# DacAmpl.net
KiCad netlist of a schematic drawn in Altium Designer
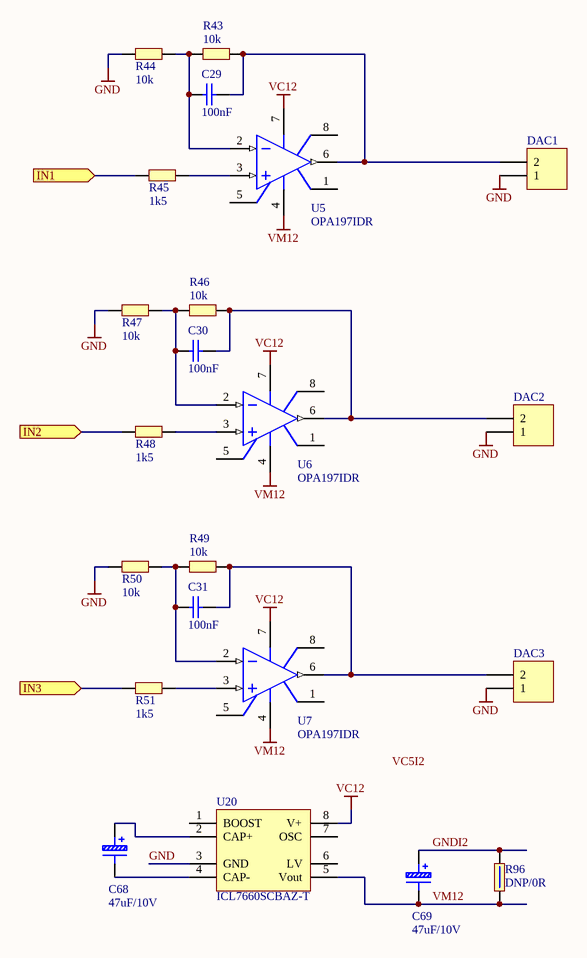
[diagram p0: DacAmpl.SchDoc]

(export (version "E")
  (design (tool "Eeschema 10.0.6"))
  (components
    (comp (ref "C29")
      (value "100nF")
      (footprint "0603C")
      (description "Capacitor,100nF,16V,X7R,10%,0402,YAGEO")
      (libsource (lib "MCD_TOOLS") (part "Cap_100nF_X7R_10%_0402"))
    )
    (comp (ref "C30")
      (value "100nF")
      (footprint "0603C")
      (description "Capacitor,100nF,16V,X7R,10%,0402,YAGEO")
      (libsource (lib "MCD_TOOLS") (part "Cap_100nF_X7R_10%_0402"))
    )
    (comp (ref "C31")
      (value "100nF")
      (footprint "0603C")
      (description "Capacitor,100nF,16V,X7R,10%,0402,YAGEO")
      (libsource (lib "MCD_TOOLS") (part "Cap_100nF_X7R_10%_0402"))
    )
    (comp (ref "C68") (value "47uF/10V") (footprint "CAP_C") (libsource (lib "GkSchlib") (part "CapTantal")))
    (comp (ref "C69") (value "47uF/10V") (footprint "CAP_C") (libsource (lib "GkSchlib") (part "CapTantal")))
    (comp (ref "DAC1")
      (value "Header 2")
      (footprint "JST-B2B-XH-A")
      (description "Header, 2-Pin")
      (fields (field (name "PUBLISHER") "Altium Limited"))
      (libsource (lib "Miscellaneous Connectors") (part "Header 2"))
    )
    (comp (ref "DAC2")
      (value "Header 2")
      (footprint "JST-B2B-XH-A")
      (description "Header, 2-Pin")
      (fields (field (name "PUBLISHER") "Altium Limited"))
      (libsource (lib "Miscellaneous Connectors") (part "Header 2"))
    )
    (comp (ref "DAC3")
      (value "Header 2")
      (footprint "JST-B2B-XH-A")
      (description "Header, 2-Pin")
      (fields (field (name "PUBLISHER") "Altium Limited"))
      (libsource (lib "Miscellaneous Connectors") (part "Header 2"))
    )
    (comp (ref "R43") (value "10k") (footprint "0603R") (libsource (lib "*") (part "RES3")))
    (comp (ref "R44") (value "10k") (footprint "0603R") (libsource (lib "*") (part "RES3")))
    (comp (ref "R45") (value "1k5") (footprint "0603R") (libsource (lib "*") (part "RES3")))
    (comp (ref "R46") (value "10k") (footprint "0603R") (libsource (lib "*") (part "RES3")))
    (comp (ref "R47") (value "10k") (footprint "0603R") (libsource (lib "*") (part "RES3")))
    (comp (ref "R48") (value "1k5") (footprint "0603R") (libsource (lib "*") (part "RES3")))
    (comp (ref "R49") (value "10k") (footprint "0603R") (libsource (lib "*") (part "RES3")))
    (comp (ref "R50") (value "10k") (footprint "0603R") (libsource (lib "*") (part "RES3")))
    (comp (ref "R51") (value "1k5") (footprint "0603R") (libsource (lib "*") (part "RES3")))
    (comp (ref "R96") (value "DNP/0R") (footprint "0603R") (libsource (lib "GkSchlib") (part "RES3Z")))
    (comp (ref "U5")
      (value "OPA197IDR")
      (footprint "SO8")
      (description "FET Operational Amplifier")
      (fields (field (name "PUBLISHER") "Altium Limited"))
      (libsource (lib "Miscellaneous Devices") (part "Op Amp"))
    )
    (comp (ref "U6")
      (value "OPA197IDR")
      (footprint "SO8")
      (description "FET Operational Amplifier")
      (fields (field (name "PUBLISHER") "Altium Limited"))
      (libsource (lib "Miscellaneous Devices") (part "Op Amp"))
    )
    (comp (ref "U7")
      (value "OPA197IDR")
      (footprint "SO8")
      (description "FET Operational Amplifier")
      (fields (field (name "PUBLISHER") "Altium Limited"))
      (libsource (lib "Miscellaneous Devices") (part "Op Amp"))
    )
    (comp (ref "U20")
      (value "ICL7660SCBAZ-T")
      (footprint "SO8")
      (libsource (lib "GkSchlib") (part "ICL7660"))
    )
  )
  (nets
    (net (code "1") (name "/GNDI2") (class "Default")
      (node (ref "C69") (pin "2") (pintype "passive"))
      (node (ref "R96") (pin "1") (pintype "passive"))
    )
    (net (code "2") (name "/IN1") (class "Default") (node (ref "R45") (pin "1") (pintype "passive")))
    (net (code "3") (name "/IN2") (class "Default") (node (ref "R48") (pin "1") (pintype "passive")))
    (net (code "4") (name "/IN3") (class "Default") (node (ref "R51") (pin "1") (pintype "passive")))
    (net (code "6") (name "GND") (class "Default")
      (node (ref "DAC1") (pin "1") (pinfunction "1_1") (pintype "passive"))
      (node (ref "DAC2") (pin "1") (pinfunction "1_1") (pintype "passive"))
      (node (ref "DAC3") (pin "1") (pinfunction "1_1") (pintype "passive"))
      (node (ref "R44") (pin "1") (pintype "passive"))
      (node (ref "R47") (pin "1") (pintype "passive"))
      (node (ref "R50") (pin "1") (pintype "passive"))
      (node (ref "U20") (pin "3") (pinfunction "GND_3") (pintype "passive"))
    )
    (net (code "7") (name "Net-(U5-IN+)") (class "Default")
      (node (ref "R45") (pin "2") (pintype "passive"))
      (node (ref "U5") (pin "3") (pinfunction "IN+_3") (pintype "input"))
    )
    (net (code "8") (name "Net-(U5-IN-)") (class "Default")
      (node (ref "C29") (pin "2") (pinfunction "2_2") (pintype "passive"))
      (node (ref "R43") (pin "1") (pintype "passive"))
      (node (ref "R44") (pin "2") (pintype "passive"))
      (node (ref "U5") (pin "2") (pinfunction "IN-_2") (pintype "input"))
    )
    (net (code "9") (name "Net-(U5-OUT)") (class "Default")
      (node (ref "C29") (pin "1") (pinfunction "1_1") (pintype "passive"))
      (node (ref "DAC1") (pin "2") (pinfunction "2_2") (pintype "passive"))
      (node (ref "R43") (pin "2") (pintype "passive"))
      (node (ref "U5") (pin "6") (pinfunction "OUT_6") (pintype "output"))
    )
    (net (code "10") (name "Net-(U6-IN+)") (class "Default")
      (node (ref "R48") (pin "2") (pintype "passive"))
      (node (ref "U6") (pin "3") (pinfunction "IN+_3") (pintype "input"))
    )
    (net (code "11") (name "Net-(U6-IN-)") (class "Default")
      (node (ref "C30") (pin "2") (pinfunction "2_2") (pintype "passive"))
      (node (ref "R46") (pin "1") (pintype "passive"))
      (node (ref "R47") (pin "2") (pintype "passive"))
      (node (ref "U6") (pin "2") (pinfunction "IN-_2") (pintype "input"))
    )
    (net (code "12") (name "Net-(U6-OUT)") (class "Default")
      (node (ref "C30") (pin "1") (pinfunction "1_1") (pintype "passive"))
      (node (ref "DAC2") (pin "2") (pinfunction "2_2") (pintype "passive"))
      (node (ref "R46") (pin "2") (pintype "passive"))
      (node (ref "U6") (pin "6") (pinfunction "OUT_6") (pintype "output"))
    )
    (net (code "13") (name "Net-(U7-IN+)") (class "Default")
      (node (ref "R51") (pin "2") (pintype "passive"))
      (node (ref "U7") (pin "3") (pinfunction "IN+_3") (pintype "input"))
    )
    (net (code "14") (name "Net-(U7-IN-)") (class "Default")
      (node (ref "C31") (pin "2") (pinfunction "2_2") (pintype "passive"))
      (node (ref "R49") (pin "1") (pintype "passive"))
      (node (ref "R50") (pin "2") (pintype "passive"))
      (node (ref "U7") (pin "2") (pinfunction "IN-_2") (pintype "input"))
    )
    (net (code "15") (name "Net-(U7-OUT)") (class "Default")
      (node (ref "C31") (pin "1") (pinfunction "1_1") (pintype "passive"))
      (node (ref "DAC3") (pin "2") (pinfunction "2_2") (pintype "passive"))
      (node (ref "R49") (pin "2") (pintype "passive"))
      (node (ref "U7") (pin "6") (pinfunction "OUT_6") (pintype "output"))
    )
    (net (code "16") (name "Net-(U20-CAP+)") (class "Default")
      (node (ref "C68") (pin "2") (pintype "passive"))
      (node (ref "U20") (pin "2") (pinfunction "CAP+_2") (pintype "passive"))
    )
    (net (code "17") (name "Net-(U20-CAP-)") (class "Default")
      (node (ref "C68") (pin "1") (pintype "passive"))
      (node (ref "U20") (pin "4") (pinfunction "CAP-_4") (pintype "passive"))
    )
    (net (code "18") (name "VC12") (class "Default")
      (node (ref "U20") (pin "8") (pinfunction "V+_8") (pintype "passive"))
      (node (ref "U5") (pin "7") (pinfunction "V+_7") (pintype "power_in"))
      (node (ref "U6") (pin "7") (pinfunction "V+_7") (pintype "power_in"))
      (node (ref "U7") (pin "7") (pinfunction "V+_7") (pintype "power_in"))
    )
    (net (code "19") (name "VM12") (class "Default")
      (node (ref "C69") (pin "1") (pintype "passive"))
      (node (ref "R96") (pin "2") (pintype "passive"))
      (node (ref "U20") (pin "5") (pinfunction "Vout_5") (pintype "passive"))
      (node (ref "U5") (pin "4") (pinfunction "V-_4") (pintype "power_in"))
      (node (ref "U6") (pin "4") (pinfunction "V-_4") (pintype "power_in"))
      (node (ref "U7") (pin "4") (pinfunction "V-_4") (pintype "power_in"))
    )
    (net (code "20") (name "unconnected-(U5-OS_NUL-Pad1)") (class "Default")
      (node (ref "U5") (pin "1") (pinfunction "OS_NUL_1") (pintype "passive"))
    )
    (net (code "21") (name "unconnected-(U5-OS_NUL-Pad5)") (class "Default")
      (node (ref "U5") (pin "5") (pinfunction "OS_NUL_5") (pintype "passive"))
    )
    (net (code "22") (name "unconnected-(U5-TAB-Pad8)") (class "Default")
      (node (ref "U5") (pin "8") (pinfunction "TAB_8") (pintype "passive"))
    )
    (net (code "23") (name "unconnected-(U6-OS_NUL-Pad1)") (class "Default")
      (node (ref "U6") (pin "1") (pinfunction "OS_NUL_1") (pintype "passive"))
    )
    (net (code "24") (name "unconnected-(U6-OS_NUL-Pad5)") (class "Default")
      (node (ref "U6") (pin "5") (pinfunction "OS_NUL_5") (pintype "passive"))
    )
    (net (code "25") (name "unconnected-(U6-TAB-Pad8)") (class "Default")
      (node (ref "U6") (pin "8") (pinfunction "TAB_8") (pintype "passive"))
    )
    (net (code "26") (name "unconnected-(U7-OS_NUL-Pad1)") (class "Default")
      (node (ref "U7") (pin "1") (pinfunction "OS_NUL_1") (pintype "passive"))
    )
    (net (code "27") (name "unconnected-(U7-OS_NUL-Pad5)") (class "Default")
      (node (ref "U7") (pin "5") (pinfunction "OS_NUL_5") (pintype "passive"))
    )
    (net (code "28") (name "unconnected-(U7-TAB-Pad8)") (class "Default")
      (node (ref "U7") (pin "8") (pinfunction "TAB_8") (pintype "passive"))
    )
    (net (code "29") (name "unconnected-(U20-BOOST-Pad1)") (class "Default")
      (node (ref "U20") (pin "1") (pinfunction "BOOST_1") (pintype "passive"))
    )
    (net (code "30") (name "unconnected-(U20-LV-Pad6)") (class "Default")
      (node (ref "U20") (pin "6") (pinfunction "LV_6") (pintype "passive"))
    )
    (net (code "31") (name "unconnected-(U20-OSC-Pad7)") (class "Default")
      (node (ref "U20") (pin "7") (pinfunction "OSC_7") (pintype "passive"))
    )
  )
)
